# GeneBird_ESP_8266_Schmatic.net
KiCad netlist of a schematic drawn in EasyEDA
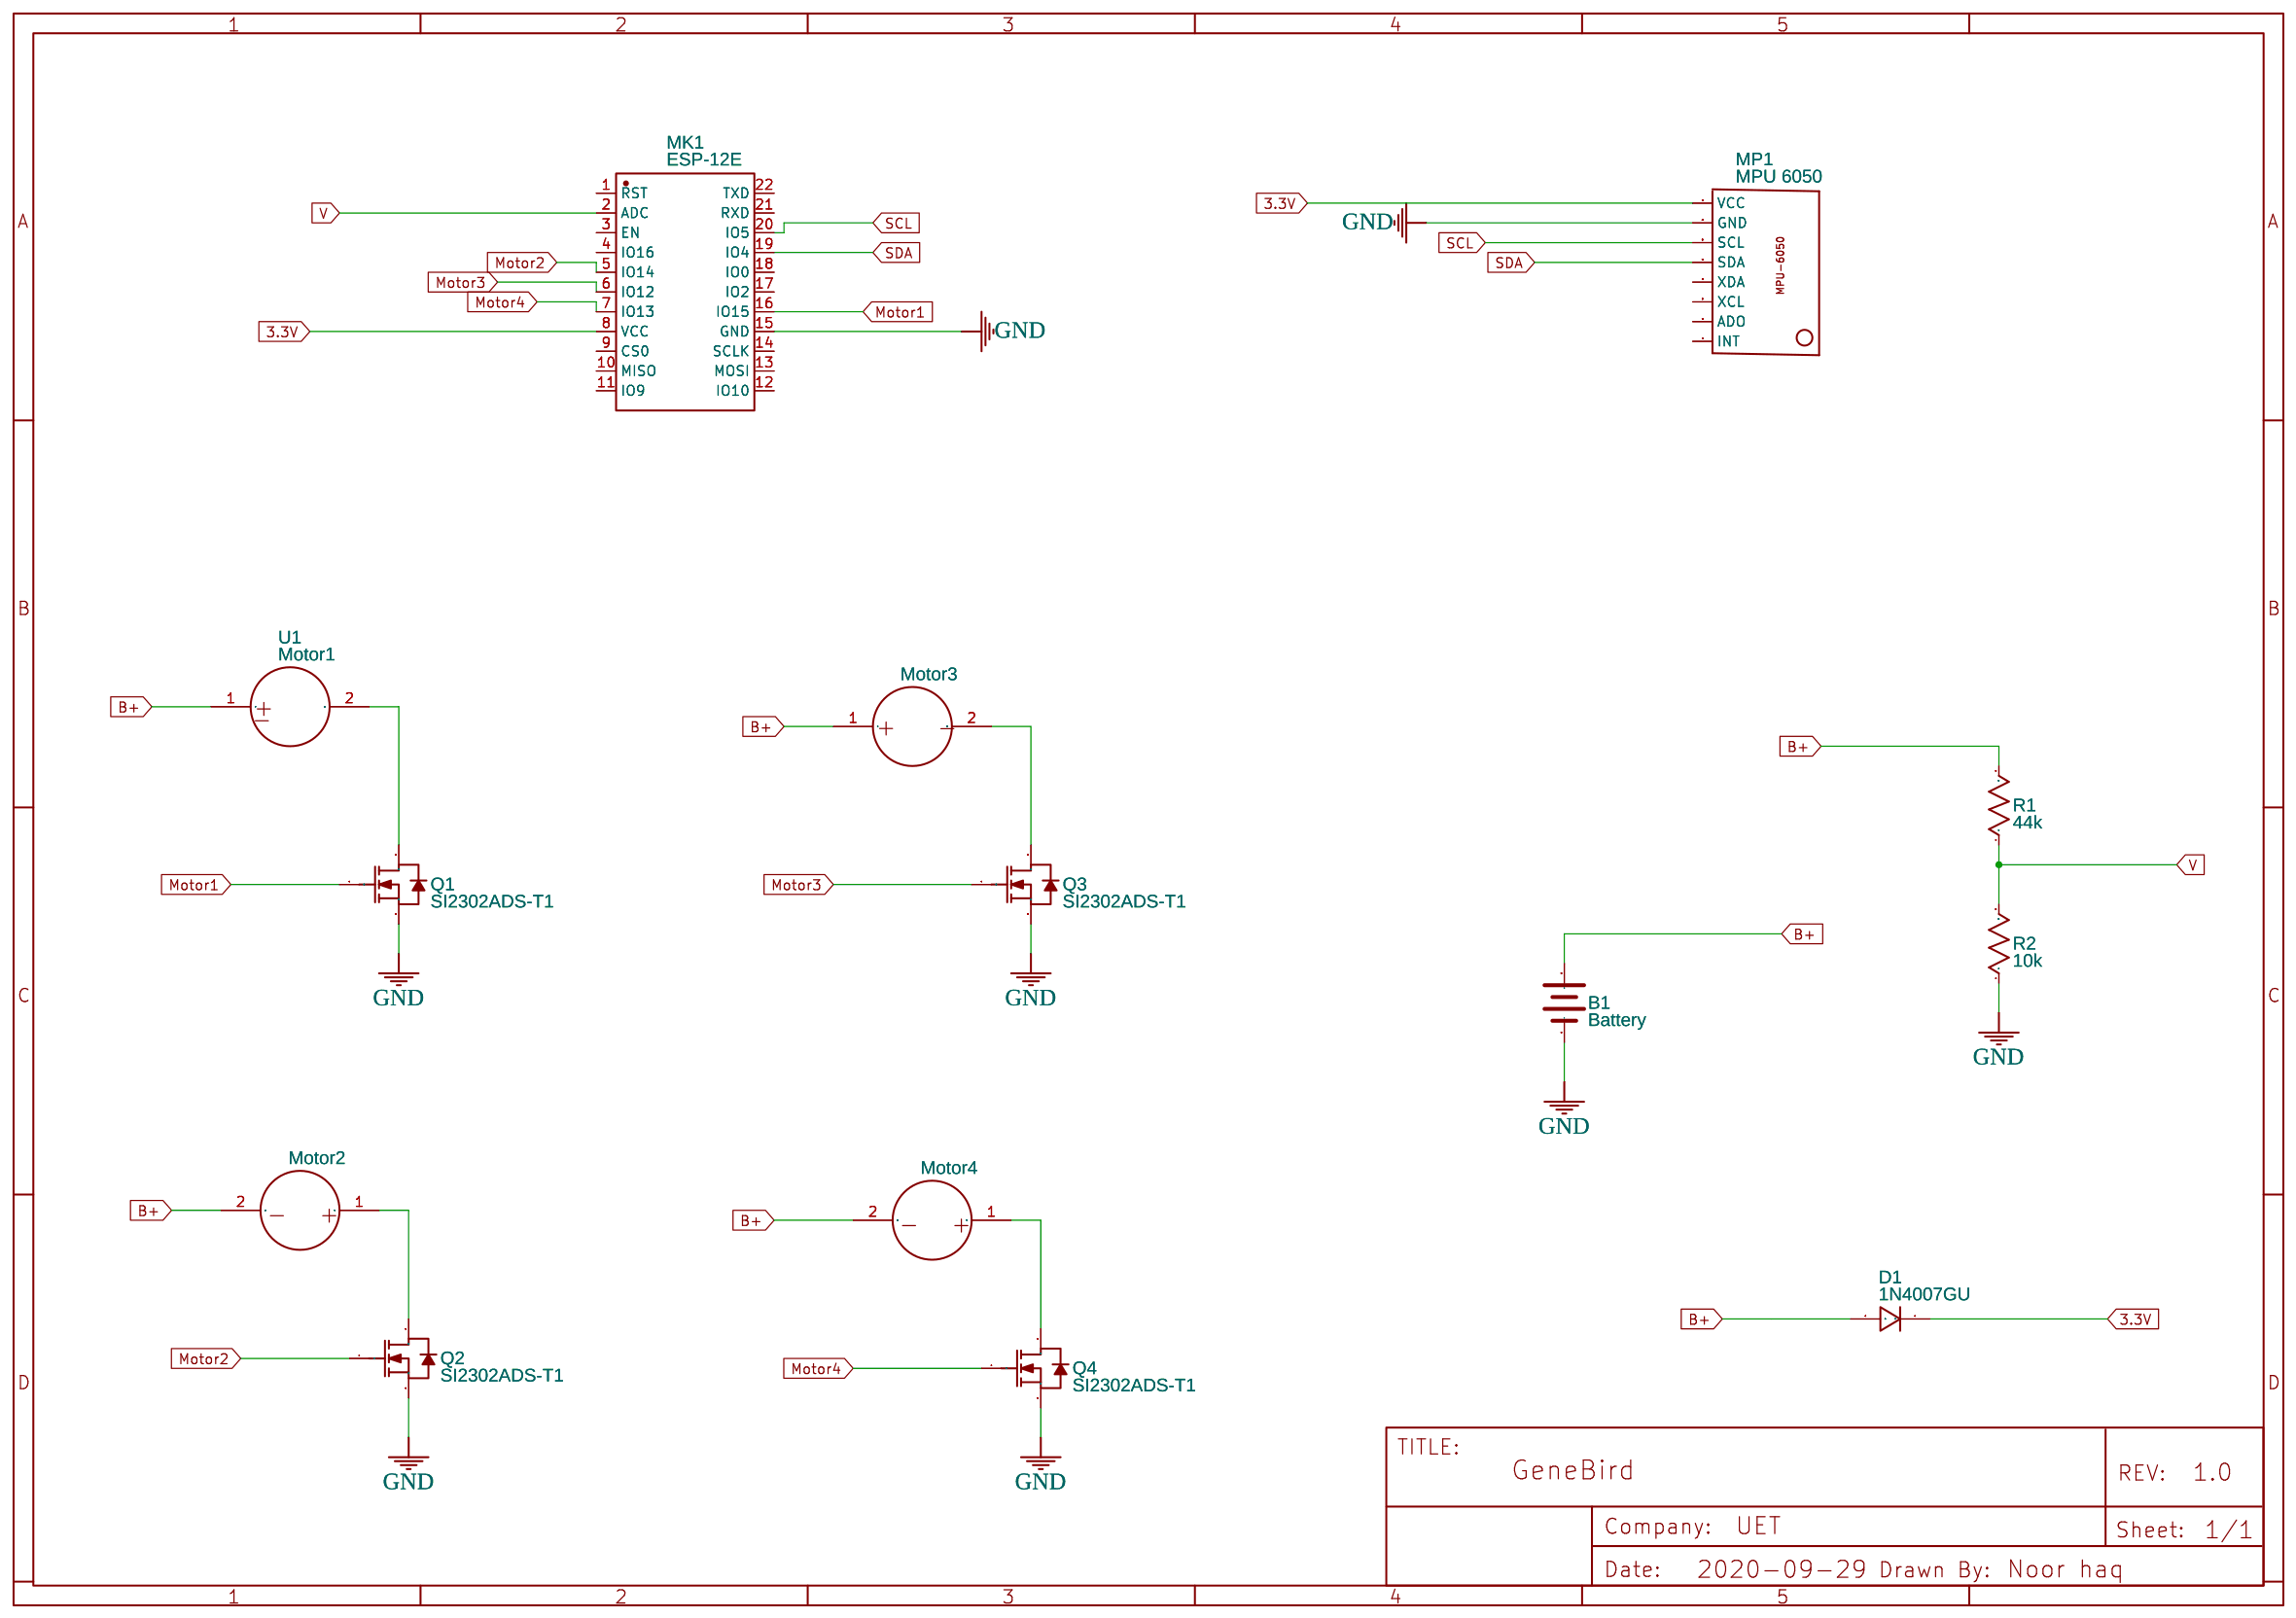
[diagram p0: schematic sheet]

(export (version "E")
  (design (tool "Eeschema 10.0.6"))
  (components
    (comp (ref "B1")
      (value "Battery")
      (fields (field (name "BOM_Supplier Part") "undefined"))
      (libsource (lib "") (part "Battery"))
    )
    (comp (ref "D1")
      (value "1N4007GU")
      (fields (field (name "BOM_Supplier Part") "C189226"))
      (libsource (lib "") (part "1N4007GU"))
    )
    (comp (ref "MK1")
      (value "ESP-12E")
      (fields (field (name "BOM_Supplier Part") "C89297"))
      (libsource (lib "") (part "ESP-12E"))
    )
    (comp (ref "MP1") (value "MPU 6050") (libsource (lib "") (part "MPU 6050")))
    (comp (ref "Q1")
      (value "SI2302ADS-T1")
      (fields (field (name "BOM_Supplier Part") "C725156"))
      (libsource (lib "") (part "SI2302ADS-T1"))
    )
    (comp (ref "Q2")
      (value "SI2302ADS-T1")
      (fields (field (name "BOM_Supplier Part") "C725156"))
      (libsource (lib "") (part "SI2302ADS-T1"))
    )
    (comp (ref "Q3")
      (value "SI2302ADS-T1")
      (fields (field (name "BOM_Supplier Part") "C725156"))
      (libsource (lib "") (part "SI2302ADS-T1"))
    )
    (comp (ref "Q4")
      (value "SI2302ADS-T1")
      (fields (field (name "BOM_Supplier Part") "C725156"))
      (libsource (lib "") (part "SI2302ADS-T1"))
    )
    (comp (ref "R1") (value "44k") (libsource (lib "") (part "R_0603_US")))
    (comp (ref "R2") (value "10k") (libsource (lib "") (part "R_0603_US")))
    (comp (ref "U1") (value "Motor1") (libsource (lib "") (part "TWO WIRE HOLES 5MM SPACING")))
    (comp (ref "U2") (value "Motor2") (libsource (lib "") (part "TWO WIRE HOLES 5MM SPACING_1")))
    (comp (ref "U3") (value "Motor3") (libsource (lib "") (part "TWO WIRE HOLES 5MM SPACING_2")))
    (comp (ref "U4") (value "Motor4") (libsource (lib "") (part "TWO WIRE HOLES 5MM SPACING_1")))
  )
  (nets
    (net (code "1") (name "3.3V") (class "Default")
      (node (ref "D1") (pin "1") (pinfunction "1_1") (pintype "unspecified"))
      (node (ref "MK1") (pin "8") (pinfunction "VCC_8") (pintype "unspecified"))
      (node (ref "MP1") (pin "VCC") (pinfunction "VCC_VCC") (pintype "unspecified"))
    )
    (net (code "2") (name "B+") (class "Default")
      (node (ref "B1") (pin "+VE") (pinfunction "+_+VE") (pintype "unspecified"))
      (node (ref "D1") (pin "2") (pinfunction "2_2") (pintype "unspecified"))
      (node (ref "R1") (pin "2") (pinfunction "2_2") (pintype "unspecified"))
      (node (ref "U1") (pin "1") (pinfunction "1_1") (pintype "unspecified"))
      (node (ref "U2") (pin "2") (pinfunction "2_2") (pintype "unspecified"))
      (node (ref "U3") (pin "1") (pinfunction "1_1") (pintype "unspecified"))
      (node (ref "U4") (pin "2") (pinfunction "2_2") (pintype "unspecified"))
    )
    (net (code "3") (name "GND") (class "Default")
      (node (ref "B1") (pin "-VE") (pinfunction "-_-VE") (pintype "unspecified"))
      (node (ref "MK1") (pin "15") (pinfunction "GND_15") (pintype "unspecified"))
      (node (ref "MP1") (pin "GND") (pinfunction "GND_GND") (pintype "unspecified"))
      (node (ref "Q1") (pin "2") (pinfunction "S_2") (pintype "unspecified"))
      (node (ref "Q2") (pin "2") (pinfunction "S_2") (pintype "unspecified"))
      (node (ref "Q3") (pin "2") (pinfunction "S_2") (pintype "unspecified"))
      (node (ref "Q4") (pin "2") (pinfunction "S_2") (pintype "unspecified"))
      (node (ref "R2") (pin "1") (pinfunction "1_1") (pintype "unspecified"))
    )
    (net (code "4") (name "Motor1") (class "Default")
      (node (ref "MK1") (pin "16") (pinfunction "IO15_16") (pintype "unspecified"))
      (node (ref "Q1") (pin "1") (pinfunction "G_1") (pintype "unspecified"))
    )
    (net (code "5") (name "Motor2") (class "Default")
      (node (ref "MK1") (pin "5") (pinfunction "IO14_5") (pintype "unspecified"))
      (node (ref "Q2") (pin "1") (pinfunction "G_1") (pintype "unspecified"))
    )
    (net (code "6") (name "Motor3") (class "Default")
      (node (ref "MK1") (pin "6") (pinfunction "IO12_6") (pintype "unspecified"))
      (node (ref "Q3") (pin "1") (pinfunction "G_1") (pintype "unspecified"))
    )
    (net (code "7") (name "Motor4") (class "Default")
      (node (ref "MK1") (pin "7") (pinfunction "IO13_7") (pintype "unspecified"))
      (node (ref "Q4") (pin "1") (pinfunction "G_1") (pintype "unspecified"))
    )
    (net (code "8") (name "Net-(Q1-D)") (class "Default")
      (node (ref "Q1") (pin "3") (pinfunction "D_3") (pintype "unspecified"))
      (node (ref "U1") (pin "2") (pinfunction "2_2") (pintype "unspecified"))
    )
    (net (code "9") (name "Net-(Q2-D)") (class "Default")
      (node (ref "Q2") (pin "3") (pinfunction "D_3") (pintype "unspecified"))
      (node (ref "U2") (pin "1") (pinfunction "1_1") (pintype "unspecified"))
    )
    (net (code "10") (name "Net-(Q3-D)") (class "Default")
      (node (ref "Q3") (pin "3") (pinfunction "D_3") (pintype "unspecified"))
      (node (ref "U3") (pin "2") (pinfunction "2_2") (pintype "unspecified"))
    )
    (net (code "11") (name "Net-(Q4-D)") (class "Default")
      (node (ref "Q4") (pin "3") (pinfunction "D_3") (pintype "unspecified"))
      (node (ref "U4") (pin "1") (pinfunction "1_1") (pintype "unspecified"))
    )
    (net (code "12") (name "SCL") (class "Default")
      (node (ref "MK1") (pin "20") (pinfunction "IO5_20") (pintype "unspecified"))
      (node (ref "MP1") (pin "SCL") (pinfunction "SCL_SCL") (pintype "unspecified"))
    )
    (net (code "13") (name "SDA") (class "Default")
      (node (ref "MK1") (pin "19") (pinfunction "IO4_19") (pintype "unspecified"))
      (node (ref "MP1") (pin "SDA") (pinfunction "SDA_SDA") (pintype "unspecified"))
    )
    (net (code "14") (name "V") (class "Default")
      (node (ref "MK1") (pin "2") (pinfunction "ADC_2") (pintype "unspecified"))
      (node (ref "R1") (pin "1") (pinfunction "1_1") (pintype "unspecified"))
      (node (ref "R2") (pin "2") (pinfunction "2_2") (pintype "unspecified"))
    )
    (net (code "15") (name "unconnected-(MK1-CS0-Pad9)") (class "Default")
      (node (ref "MK1") (pin "9") (pinfunction "CS0_9") (pintype "unspecified"))
    )
    (net (code "16") (name "unconnected-(MK1-EN-Pad3)") (class "Default")
      (node (ref "MK1") (pin "3") (pinfunction "EN_3") (pintype "unspecified"))
    )
    (net (code "17") (name "unconnected-(MK1-IO0-Pad18)") (class "Default")
      (node (ref "MK1") (pin "18") (pinfunction "IO0_18") (pintype "unspecified"))
    )
    (net (code "18") (name "unconnected-(MK1-IO2-Pad17)") (class "Default")
      (node (ref "MK1") (pin "17") (pinfunction "IO2_17") (pintype "unspecified"))
    )
    (net (code "19") (name "unconnected-(MK1-IO9-Pad11)") (class "Default")
      (node (ref "MK1") (pin "11") (pinfunction "IO9_11") (pintype "unspecified"))
    )
    (net (code "20") (name "unconnected-(MK1-IO10-Pad12)") (class "Default")
      (node (ref "MK1") (pin "12") (pinfunction "IO10_12") (pintype "unspecified"))
    )
    (net (code "21") (name "unconnected-(MK1-IO16-Pad4)") (class "Default")
      (node (ref "MK1") (pin "4") (pinfunction "IO16_4") (pintype "unspecified"))
    )
    (net (code "22") (name "unconnected-(MK1-MISO-Pad10)") (class "Default")
      (node (ref "MK1") (pin "10") (pinfunction "MISO_10") (pintype "unspecified"))
    )
    (net (code "23") (name "unconnected-(MK1-MOSI-Pad13)") (class "Default")
      (node (ref "MK1") (pin "13") (pinfunction "MOSI_13") (pintype "unspecified"))
    )
    (net (code "24") (name "unconnected-(MK1-RST-Pad1)") (class "Default")
      (node (ref "MK1") (pin "1") (pinfunction "RST_1") (pintype "unspecified"))
    )
    (net (code "25") (name "unconnected-(MK1-RXD-Pad21)") (class "Default")
      (node (ref "MK1") (pin "21") (pinfunction "RXD_21") (pintype "unspecified"))
    )
    (net (code "26") (name "unconnected-(MK1-SCLK-Pad14)") (class "Default")
      (node (ref "MK1") (pin "14") (pinfunction "SCLK_14") (pintype "unspecified"))
    )
    (net (code "27") (name "unconnected-(MK1-TXD-Pad22)") (class "Default")
      (node (ref "MK1") (pin "22") (pinfunction "TXD_22") (pintype "unspecified"))
    )
    (net (code "28") (name "unconnected-(MP1-PadADO)") (class "Default")
      (node (ref "MP1") (pin "ADO") (pinfunction "ADO_ADO") (pintype "unspecified"))
    )
    (net (code "29") (name "unconnected-(MP1-PadINT)") (class "Default")
      (node (ref "MP1") (pin "INT") (pinfunction "INT_INT") (pintype "unspecified"))
    )
    (net (code "30") (name "unconnected-(MP1-PadXCL)") (class "Default")
      (node (ref "MP1") (pin "XCL") (pinfunction "XCL_XCL") (pintype "unspecified"))
    )
    (net (code "31") (name "unconnected-(MP1-PadXDA)") (class "Default")
      (node (ref "MP1") (pin "XDA") (pinfunction "XDA_XDA") (pintype "unspecified"))
    )
  )
)
